# usb_breakout.net
KiCad netlist of a schematic drawn in EAGLE
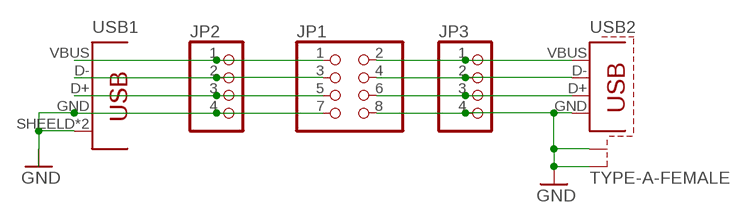
[diagram p0: schematic, sheet 1]

(export (version "E")
  (design (tool "Eeschema 10.0.6"))
  (components
    (comp (ref "JP1")
      (value "PINHD-2X4")
      (footprint "eagle-import:2X04")
      (libsource (lib "eagle-import") (part "PINHD-2X4"))
    )
    (comp (ref "JP2")
      (value "PINHD-1X4")
      (footprint "eagle-import:1X04")
      (libsource (lib "eagle-import") (part "PINHD-1X4"))
    )
    (comp (ref "JP3")
      (value "PINHD-1X4")
      (footprint "eagle-import:1X04")
      (libsource (lib "eagle-import") (part "PINHD-1X4"))
    )
    (comp (ref "USB1")
      (value "TYPE-A-MALE-SHILED")
      (footprint "eagle-import:TYPE-A-MALE")
      (libsource (lib "eagle-import") (part "TYPE-A-MALE-SHILED"))
    )
    (comp (ref "USB2")
      (value "TYPE-A-FEMALE")
      (footprint "eagle-import:TYPE-A-FEMALE")
      (libsource (lib "eagle-import") (part "TYPE-A-FEMALE"))
    )
  )
  (nets
    (net (code "1") (name "GND") (class "Default")
      (node (ref "JP1") (pin "7") (pinfunction "7_7") (pintype "passive"))
      (node (ref "JP1") (pin "8") (pinfunction "8_8") (pintype "passive"))
      (node (ref "JP2") (pin "4") (pinfunction "4_4") (pintype "passive"))
      (node (ref "JP3") (pin "4") (pinfunction "4_4") (pintype "passive"))
      (node (ref "USB1") (pin "GND") (pinfunction "4_GND") (pintype "power_in"))
      (node (ref "USB1") (pin "SHEELD") (pinfunction "5_SHEELD") (pintype "passive"))
      (node (ref "USB1") (pin "SHEELD2") (pinfunction "5_SHEELD2") (pintype "passive"))
      (node (ref "USB2") (pin "GND") (pinfunction "GND_GND") (pintype "passive"))
      (node (ref "USB2") (pin "S1") (pinfunction "S1_S1") (pintype "passive"))
      (node (ref "USB2") (pin "S2") (pinfunction "S2_S2") (pintype "passive"))
    )
    (net (code "2") (name "Net-(JP1-Pad4)") (class "Default")
      (node (ref "JP1") (pin "4") (pinfunction "4_4") (pintype "passive"))
      (node (ref "JP3") (pin "2") (pinfunction "2_2") (pintype "passive"))
      (node (ref "USB2") (pin "D-") (pinfunction "D-_D-") (pintype "passive"))
    )
    (net (code "3") (name "Net-(JP1-Pad6)") (class "Default")
      (node (ref "JP1") (pin "6") (pinfunction "6_6") (pintype "passive"))
      (node (ref "JP3") (pin "3") (pinfunction "3_3") (pintype "passive"))
      (node (ref "USB2") (pin "D+") (pinfunction "D+_D+") (pintype "passive"))
    )
    (net (code "4") (name "Net-(USB1-1)") (class "Default")
      (node (ref "JP1") (pin "1") (pinfunction "1_1") (pintype "passive"))
      (node (ref "JP2") (pin "1") (pinfunction "1_1") (pintype "passive"))
      (node (ref "USB1") (pin "VBUS") (pinfunction "1_VBUS") (pintype "power_in"))
    )
    (net (code "5") (name "Net-(USB1-2)") (class "Default")
      (node (ref "JP1") (pin "3") (pinfunction "3_3") (pintype "passive"))
      (node (ref "JP2") (pin "2") (pinfunction "2_2") (pintype "passive"))
      (node (ref "USB1") (pin "D-") (pinfunction "2_D-") (pintype "passive"))
    )
    (net (code "6") (name "Net-(USB1-3)") (class "Default")
      (node (ref "JP1") (pin "5") (pinfunction "5_5") (pintype "passive"))
      (node (ref "JP2") (pin "3") (pinfunction "3_3") (pintype "passive"))
      (node (ref "USB1") (pin "D+") (pinfunction "3_D+") (pintype "passive"))
    )
    (net (code "7") (name "Net-(USB2-VCC)") (class "Default")
      (node (ref "JP1") (pin "2") (pinfunction "2_2") (pintype "passive"))
      (node (ref "JP3") (pin "1") (pinfunction "1_1") (pintype "passive"))
      (node (ref "USB2") (pin "VBUS") (pinfunction "VCC_VBUS") (pintype "passive"))
    )
  )
)
